# PDU.net
KiCad netlist of a schematic drawn in EAGLE
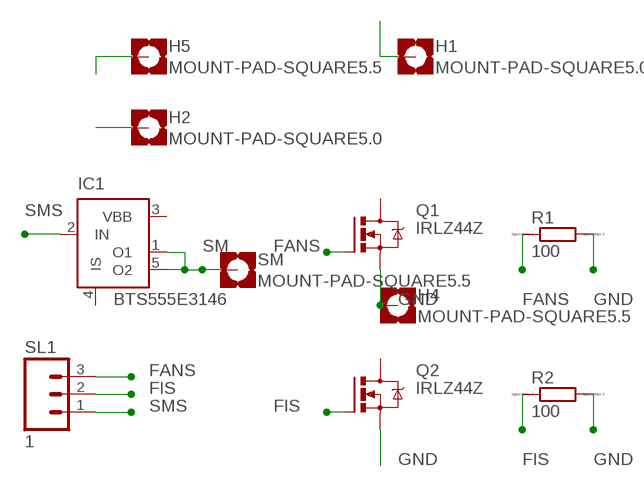
[diagram p0: schematic, sheet 1]

(export (version "E")
  (design (tool "Eeschema 10.0.6"))
  (components
    (comp (ref "H1")
      (value "MOUNT-PAD-SQUARE5.0")
      (footprint "eagle-import:5,0-PAD-SQUARE")
      (libsource (lib "eagle-import") (part "MOUNT-PAD-SQUARE5.0"))
    )
    (comp (ref "H2")
      (value "MOUNT-PAD-SQUARE5.0")
      (footprint "eagle-import:5,0-PAD-SQUARE")
      (libsource (lib "eagle-import") (part "MOUNT-PAD-SQUARE5.0"))
    )
    (comp (ref "H4")
      (value "MOUNT-PAD-SQUARE5.5")
      (footprint "eagle-import:5,5-PAD-SQUARE")
      (libsource (lib "eagle-import") (part "MOUNT-PAD-SQUARE5.5"))
    )
    (comp (ref "H5")
      (value "MOUNT-PAD-SQUARE5.5")
      (footprint "eagle-import:5,5-PAD-SQUARE")
      (libsource (lib "eagle-import") (part "MOUNT-PAD-SQUARE5.5"))
    )
    (comp (ref "IC1")
      (value "BTS555E3146")
      (footprint "eagle-import:TO220-52")
      (libsource (lib "eagle-import") (part "BTS555E3146"))
    )
    (comp (ref "Q1")
      (value "IRLZ44Z")
      (footprint "eagle-import:TO220BH")
      (libsource (lib "eagle-import") (part "IRLZ44Z"))
    )
    (comp (ref "Q2")
      (value "IRLZ44Z")
      (footprint "eagle-import:TO220BH")
      (libsource (lib "eagle-import") (part "IRLZ44Z"))
    )
    (comp (ref "R1")
      (value "100")
      (footprint "eagle-import:R1206")
      (libsource (lib "eagle-import") (part "RR1206"))
    )
    (comp (ref "R2")
      (value "100")
      (footprint "eagle-import:R1206")
      (libsource (lib "eagle-import") (part "RR1206"))
    )
    (comp (ref "SL1")
      (value "1")
      (footprint "eagle-import:03P")
      (libsource (lib "eagle-import") (part "M03"))
    )
    (comp (ref "SM")
      (value "MOUNT-PAD-SQUARE5.5")
      (footprint "eagle-import:5,5-PAD-SQUARE")
      (libsource (lib "eagle-import") (part "MOUNT-PAD-SQUARE5.5"))
    )
  )
  (nets
    (net (code "1") (name "/FANS") (class "Default")
      (node (ref "Q1") (pin "G") (pinfunction "G_G") (pintype "passive"))
      (node (ref "R1") (pin "1") (pinfunction "1_1") (pintype "passive"))
      (node (ref "SL1") (pin "3") (pinfunction "3_3") (pintype "passive"))
    )
    (net (code "2") (name "/FIS") (class "Default")
      (node (ref "Q2") (pin "G") (pinfunction "G_G") (pintype "passive"))
      (node (ref "R2") (pin "1") (pinfunction "1_1") (pintype "passive"))
      (node (ref "SL1") (pin "2") (pinfunction "2_2") (pintype "passive"))
    )
    (net (code "3") (name "/GND") (class "Default")
      (node (ref "H4") (pin "B5,5") (pinfunction "MOUNT_B5,5") (pintype "passive"))
      (node (ref "Q1") (pin "S") (pinfunction "S_S") (pintype "passive"))
      (node (ref "Q2") (pin "S") (pinfunction "S_S") (pintype "passive"))
      (node (ref "R1") (pin "2") (pinfunction "2_2") (pintype "passive"))
      (node (ref "R2") (pin "2") (pinfunction "2_2") (pintype "passive"))
    )
    (net (code "4") (name "/SM") (class "Default")
      (node (ref "IC1") (pin "1") (pinfunction "O1_1") (pintype "passive"))
      (node (ref "IC1") (pin "5") (pinfunction "O2_5") (pintype "passive"))
      (node (ref "SM") (pin "B5,5") (pinfunction "MOUNT_B5,5") (pintype "passive"))
    )
    (net (code "5") (name "/SMS") (class "Default")
      (node (ref "IC1") (pin "2") (pinfunction "IN_2") (pintype "input"))
      (node (ref "SL1") (pin "1") (pinfunction "1_1") (pintype "passive"))
    )
    (net (code "6") (name "unconnected-(H1-MOUNT-PadB5)") (class "Default")
      (node (ref "H1") (pin "B5") (pinfunction "MOUNT_B5") (pintype "passive"))
    )
    (net (code "7") (name "unconnected-(H2-MOUNT-PadB5)") (class "Default")
      (node (ref "H2") (pin "B5") (pinfunction "MOUNT_B5") (pintype "passive"))
    )
    (net (code "8") (name "unconnected-(H5-MOUNT-PadB5,5)") (class "Default")
      (node (ref "H5") (pin "B5,5") (pinfunction "MOUNT_B5,5") (pintype "passive"))
    )
    (net (code "9") (name "unconnected-(IC1-IS-Pad4)") (class "Default")
      (node (ref "IC1") (pin "4") (pinfunction "IS_4") (pintype "passive"))
    )
    (net (code "10") (name "unconnected-(IC1-VBB-Pad3)") (class "Default")
      (node (ref "IC1") (pin "3") (pinfunction "VBB_3") (pintype "passive"))
    )
    (net (code "11") (name "unconnected-(Q1-PadD)") (class "Default")
      (node (ref "Q1") (pin "D") (pinfunction "D_D") (pintype "passive"))
    )
    (net (code "12") (name "unconnected-(Q2-PadD)") (class "Default")
      (node (ref "Q2") (pin "D") (pinfunction "D_D") (pintype "passive"))
    )
  )
)
